# STM32F407ZGT6Floor.net
KiCad netlist of a schematic drawn in Altium Designer
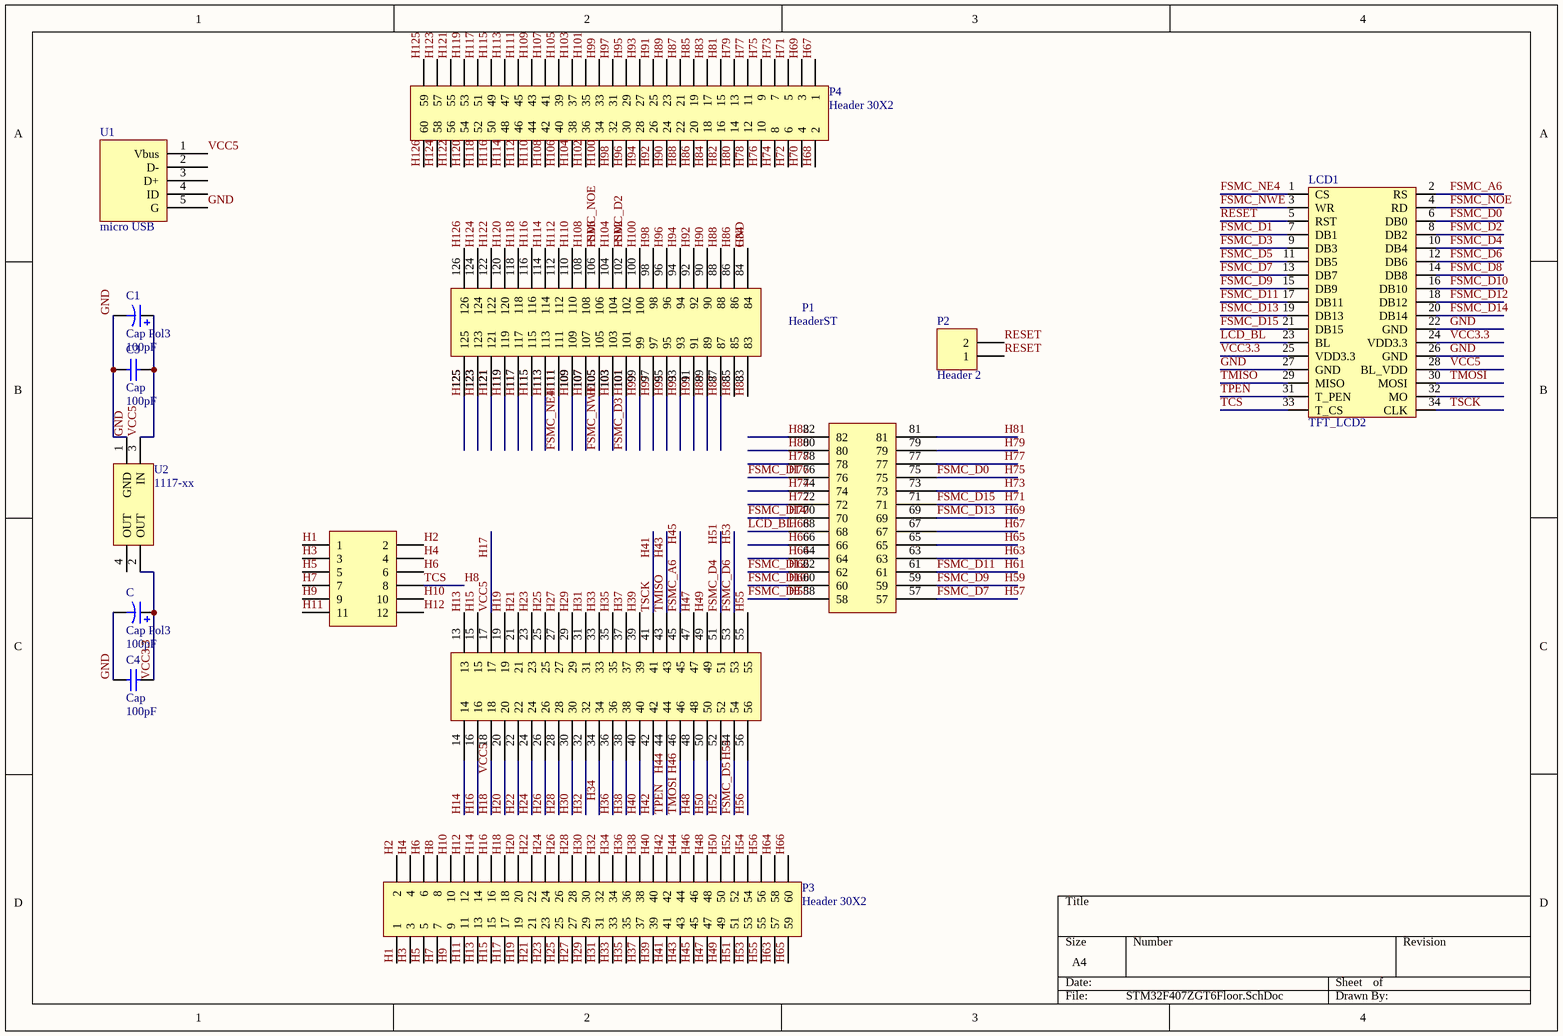
[diagram p0: STM32F407ZGT6Floor.SchDoc]

(export (version "E")
  (design (tool "Eeschema 10.0.6"))
  (components
    (comp (ref "C")
      (value "Cap Pol3")
      (footprint "CAP_SMD_3216")
      (description "Polarized Capacitor (Surface Mount)")
      (fields (field (name "ALTIUM_VALUE") "100pF") (field (name "PUBLISHER") "Altium Limited"))
      (libsource (lib "Miscellaneous Devices") (part "Cap Pol3"))
    )
    (comp (ref "C1")
      (value "Cap Pol3")
      (footprint "CAP_SMD_3216")
      (description "Polarized Capacitor (Surface Mount)")
      (fields (field (name "ALTIUM_VALUE") "100pF") (field (name "PUBLISHER") "Altium Limited"))
      (libsource (lib "Miscellaneous Devices") (part "Cap Pol3"))
    )
    (comp (ref "C3")
      (value "Cap")
      (footprint "0805C")
      (description "Capacitor")
      (fields (field (name "ALTIUM_VALUE") "100pF") (field (name "PUBLISHER") "Altium Limited"))
      (libsource (lib "Miscellaneous Devices") (part "Cap"))
    )
    (comp (ref "C4")
      (value "Cap")
      (footprint "0805C")
      (description "Capacitor")
      (fields (field (name "ALTIUM_VALUE") "100pF") (field (name "PUBLISHER") "Altium Limited"))
      (libsource (lib "Miscellaneous Devices") (part "Cap"))
    )
    (comp (ref "LCD1")
      (value "TFT_LCD2")
      (footprint "DB2*17-3.5")
      (libsource (lib "4.3TFTLCD") (part "TFT_LCD2"))
    )
    (comp (ref "P1")
      (value "HeaderST")
      (footprint "PCBComponent_1-1")
      (description "Header, 30-Pin, Dual row")
      (fields (field (name "PUBLISHER") "Altium Limited"))
      (libsource (lib "2-STM32F407ZGT6MINI原理图") (part "HeaderST"))
    )
    (comp (ref "P2")
      (value "Header 2")
      (footprint "HDR1X2")
      (description "Header, 2-Pin")
      (fields (field (name "PUBLISHER") "Altium Limited"))
      (libsource (lib "Miscellaneous Connectors") (part "Header 2"))
    )
    (comp (ref "P3")
      (value "Header 30X2")
      (footprint "HDR2X30")
      (description "Header, 30-Pin, Dual row")
      (fields (field (name "PUBLISHER") "Altium Limited"))
      (libsource (lib "") (part "Header 30X2_1"))
    )
    (comp (ref "P4")
      (value "Header 30X2")
      (footprint "HDR2X30")
      (description "Header, 30-Pin, Dual row")
      (fields (field (name "PUBLISHER") "Altium Limited"))
      (libsource (lib "Miscellaneous Connectors") (part "Header 30X2"))
    )
    (comp (ref "U1")
      (value "micro USB")
      (footprint "Micro_USB_v2 - duplicate")
      (libsource (lib "2-STM32F407ZGT6MINI原理图") (part "usb-STM"))
    )
    (comp (ref "U2")
      (value "1117-xx")
      (footprint "SOT-223_")
      (description "稳压芯片")
      (libsource (lib "unsal_Devices") (part "1117-xx"))
    )
  )
  (nets
    (net (code "1") (name "/FSMC_A6") (class "Default")
      (node (ref "LCD1") (pin "2") (pinfunction "RS_2") (pintype "passive"))
      (node (ref "P1") (pin "45") (pinfunction "45_45") (pintype "passive"))
      (node (ref "P3") (pin "45") (pinfunction "45_45") (pintype "passive"))
    )
    (net (code "2") (name "/FSMC_D0") (class "Default")
      (node (ref "LCD1") (pin "6") (pinfunction "DB0_6") (pintype "passive"))
      (node (ref "P1") (pin "75") (pinfunction "75_75") (pintype "passive"))
      (node (ref "P4") (pin "9") (pinfunction "9_9") (pintype "passive"))
    )
    (net (code "3") (name "/FSMC_D1") (class "Default")
      (node (ref "LCD1") (pin "7") (pinfunction "DB1_7") (pintype "passive"))
      (node (ref "P1") (pin "76") (pinfunction "76_76") (pintype "passive"))
      (node (ref "P4") (pin "10") (pinfunction "10_10") (pintype "passive"))
    )
    (net (code "4") (name "/FSMC_D2") (class "Default")
      (node (ref "LCD1") (pin "8") (pinfunction "DB2_8") (pintype "passive"))
      (node (ref "P1") (pin "102") (pinfunction "102_102") (pintype "passive"))
      (node (ref "P4") (pin "36") (pinfunction "36_36") (pintype "passive"))
    )
    (net (code "5") (name "/FSMC_D3") (class "Default")
      (node (ref "LCD1") (pin "9") (pinfunction "DB3_9") (pintype "passive"))
      (node (ref "P1") (pin "101") (pinfunction "101_101") (pintype "passive"))
      (node (ref "P4") (pin "35") (pinfunction "35_35") (pintype "passive"))
    )
    (net (code "6") (name "/FSMC_D4") (class "Default")
      (node (ref "LCD1") (pin "10") (pinfunction "DB4_10") (pintype "passive"))
      (node (ref "P1") (pin "51") (pinfunction "51_51") (pintype "passive"))
      (node (ref "P3") (pin "51") (pinfunction "51_51") (pintype "passive"))
    )
    (net (code "7") (name "/FSMC_D5") (class "Default")
      (node (ref "LCD1") (pin "11") (pinfunction "DB5_11") (pintype "passive"))
      (node (ref "P1") (pin "54") (pinfunction "54_54") (pintype "passive"))
      (node (ref "P3") (pin "54") (pinfunction "54_54") (pintype "passive"))
    )
    (net (code "8") (name "/FSMC_D6") (class "Default")
      (node (ref "LCD1") (pin "12") (pinfunction "DB6_12") (pintype "passive"))
      (node (ref "P1") (pin "53") (pinfunction "53_53") (pintype "passive"))
      (node (ref "P3") (pin "53") (pinfunction "53_53") (pintype "passive"))
    )
    (net (code "9") (name "/FSMC_D7") (class "Default")
      (node (ref "LCD1") (pin "13") (pinfunction "DB7_13") (pintype "passive"))
      (node (ref "P1") (pin "57") (pinfunction "57_57") (pintype "passive"))
    )
    (net (code "10") (name "/FSMC_D8") (class "Default")
      (node (ref "LCD1") (pin "14") (pinfunction "DB8_14") (pintype "passive"))
      (node (ref "P1") (pin "58") (pinfunction "58_58") (pintype "passive"))
    )
    (net (code "11") (name "/FSMC_D9") (class "Default")
      (node (ref "LCD1") (pin "15") (pinfunction "DB9_15") (pintype "passive"))
      (node (ref "P1") (pin "59") (pinfunction "59_59") (pintype "passive"))
    )
    (net (code "12") (name "/FSMC_D10") (class "Default")
      (node (ref "LCD1") (pin "16") (pinfunction "DB10_16") (pintype "passive"))
      (node (ref "P1") (pin "60") (pinfunction "60_60") (pintype "passive"))
    )
    (net (code "13") (name "/FSMC_D11") (class "Default")
      (node (ref "LCD1") (pin "17") (pinfunction "DB11_17") (pintype "passive"))
      (node (ref "P1") (pin "61") (pinfunction "61_61") (pintype "passive"))
    )
    (net (code "14") (name "/FSMC_D12") (class "Default")
      (node (ref "LCD1") (pin "18") (pinfunction "DB12_18") (pintype "passive"))
      (node (ref "P1") (pin "62") (pinfunction "62_62") (pintype "passive"))
    )
    (net (code "15") (name "/FSMC_D13") (class "Default")
      (node (ref "LCD1") (pin "19") (pinfunction "DB13_19") (pintype "passive"))
      (node (ref "P1") (pin "69") (pinfunction "69_69") (pintype "passive"))
      (node (ref "P4") (pin "3") (pinfunction "3_3") (pintype "passive"))
    )
    (net (code "16") (name "/FSMC_D14") (class "Default")
      (node (ref "LCD1") (pin "20") (pinfunction "DB14_20") (pintype "passive"))
      (node (ref "P1") (pin "70") (pinfunction "70_70") (pintype "passive"))
      (node (ref "P4") (pin "4") (pinfunction "4_4") (pintype "passive"))
    )
    (net (code "17") (name "/FSMC_D15") (class "Default")
      (node (ref "LCD1") (pin "21") (pinfunction "DB15_21") (pintype "passive"))
      (node (ref "P1") (pin "71") (pinfunction "71_71") (pintype "passive"))
      (node (ref "P4") (pin "5") (pinfunction "5_5") (pintype "passive"))
    )
    (net (code "18") (name "/FSMC_NE4") (class "Default")
      (node (ref "LCD1") (pin "1") (pinfunction "CS_1") (pintype "passive"))
      (node (ref "P1") (pin "111") (pinfunction "111_111") (pintype "passive"))
      (node (ref "P4") (pin "45") (pinfunction "45_45") (pintype "passive"))
    )
    (net (code "19") (name "/FSMC_NOE") (class "Default")
      (node (ref "LCD1") (pin "4") (pinfunction "RD_4") (pintype "passive"))
      (node (ref "P1") (pin "106") (pinfunction "106_106") (pintype "passive"))
      (node (ref "P4") (pin "40") (pinfunction "40_40") (pintype "passive"))
    )
    (net (code "20") (name "/FSMC_NWE") (class "Default")
      (node (ref "LCD1") (pin "3") (pinfunction "WR_3") (pintype "passive"))
      (node (ref "P1") (pin "105") (pinfunction "105_105") (pintype "passive"))
      (node (ref "P4") (pin "39") (pinfunction "39_39") (pintype "passive"))
    )
    (net (code "21") (name "/GND") (class "Default")
      (node (ref "C") (pin "2") (pinfunction "2_2") (pintype "passive"))
      (node (ref "C1") (pin "2") (pinfunction "2_2") (pintype "passive"))
      (node (ref "C3") (pin "1") (pinfunction "1_1") (pintype "passive"))
      (node (ref "C4") (pin "1") (pinfunction "1_1") (pintype "passive"))
      (node (ref "LCD1") (pin "22") (pinfunction "GND_22") (pintype "passive"))
      (node (ref "LCD1") (pin "26") (pinfunction "GND_26") (pintype "passive"))
      (node (ref "LCD1") (pin "27") (pinfunction "GND_27") (pintype "passive"))
      (node (ref "P1") (pin "84") (pinfunction "84_84") (pintype "passive"))
      (node (ref "P4") (pin "18") (pinfunction "18_18") (pintype "passive"))
      (node (ref "U1") (pin "5") (pinfunction "G_5") (pintype "passive"))
      (node (ref "U2") (pin "1") (pinfunction "GND_1") (pintype "passive"))
    )
    (net (code "22") (name "/H1") (class "Default")
      (node (ref "P1") (pin "1") (pinfunction "1_1") (pintype "passive"))
      (node (ref "P3") (pin "1") (pinfunction "1_1") (pintype "passive"))
    )
    (net (code "23") (name "/H2") (class "Default")
      (node (ref "P1") (pin "2") (pinfunction "2_2") (pintype "passive"))
      (node (ref "P3") (pin "2") (pinfunction "2_2") (pintype "passive"))
    )
    (net (code "24") (name "/H3") (class "Default")
      (node (ref "P1") (pin "3") (pinfunction "3_3") (pintype "passive"))
      (node (ref "P3") (pin "3") (pinfunction "3_3") (pintype "passive"))
    )
    (net (code "25") (name "/H4") (class "Default")
      (node (ref "P1") (pin "4") (pinfunction "4_4") (pintype "passive"))
      (node (ref "P3") (pin "4") (pinfunction "4_4") (pintype "passive"))
    )
    (net (code "26") (name "/H5") (class "Default")
      (node (ref "P1") (pin "5") (pinfunction "5_5") (pintype "passive"))
      (node (ref "P3") (pin "5") (pinfunction "5_5") (pintype "passive"))
    )
    (net (code "27") (name "/H6") (class "Default")
      (node (ref "P1") (pin "6") (pinfunction "6_6") (pintype "passive"))
      (node (ref "P3") (pin "6") (pinfunction "6_6") (pintype "passive"))
    )
    (net (code "28") (name "/H7") (class "Default")
      (node (ref "P1") (pin "7") (pinfunction "7_7") (pintype "passive"))
      (node (ref "P3") (pin "7") (pinfunction "7_7") (pintype "passive"))
    )
    (net (code "29") (name "/H8") (class "Default")
      (node (ref "LCD1") (pin "33") (pinfunction "T_CS_33") (pintype "passive"))
      (node (ref "P1") (pin "8") (pinfunction "8_8") (pintype "passive"))
      (node (ref "P3") (pin "8") (pinfunction "8_8") (pintype "passive"))
    )
    (net (code "30") (name "/H9") (class "Default")
      (node (ref "P1") (pin "9") (pinfunction "9_9") (pintype "passive"))
      (node (ref "P3") (pin "9") (pinfunction "9_9") (pintype "passive"))
    )
    (net (code "31") (name "/H10") (class "Default")
      (node (ref "P1") (pin "10") (pinfunction "10_10") (pintype "passive"))
      (node (ref "P3") (pin "10") (pinfunction "10_10") (pintype "passive"))
    )
    (net (code "32") (name "/H11") (class "Default")
      (node (ref "P1") (pin "11") (pinfunction "11_11") (pintype "passive"))
      (node (ref "P3") (pin "11") (pinfunction "11_11") (pintype "passive"))
    )
    (net (code "33") (name "/H12") (class "Default")
      (node (ref "P1") (pin "12") (pinfunction "12_12") (pintype "passive"))
      (node (ref "P3") (pin "12") (pinfunction "12_12") (pintype "passive"))
    )
    (net (code "34") (name "/H13") (class "Default")
      (node (ref "P1") (pin "13") (pinfunction "13_13") (pintype "passive"))
      (node (ref "P3") (pin "13") (pinfunction "13_13") (pintype "passive"))
    )
    (net (code "35") (name "/H14") (class "Default")
      (node (ref "P1") (pin "14") (pinfunction "14_14") (pintype "passive"))
      (node (ref "P3") (pin "14") (pinfunction "14_14") (pintype "passive"))
    )
    (net (code "36") (name "/H15") (class "Default")
      (node (ref "P1") (pin "15") (pinfunction "15_15") (pintype "passive"))
      (node (ref "P3") (pin "15") (pinfunction "15_15") (pintype "passive"))
    )
    (net (code "37") (name "/H16") (class "Default")
      (node (ref "P1") (pin "16") (pinfunction "16_16") (pintype "passive"))
      (node (ref "P3") (pin "16") (pinfunction "16_16") (pintype "passive"))
    )
    (net (code "38") (name "/H17") (class "Default")
      (node (ref "C1") (pin "1") (pinfunction "1_1") (pintype "passive"))
      (node (ref "C3") (pin "2") (pinfunction "2_2") (pintype "passive"))
      (node (ref "LCD1") (pin "28") (pinfunction "BL_VDD_28") (pintype "passive"))
      (node (ref "P1") (pin "17") (pinfunction "17_17") (pintype "passive"))
      (node (ref "P1") (pin "18") (pinfunction "18_18") (pintype "passive"))
      (node (ref "P3") (pin "17") (pinfunction "17_17") (pintype "passive"))
      (node (ref "P3") (pin "18") (pinfunction "18_18") (pintype "passive"))
      (node (ref "U1") (pin "1") (pinfunction "Vbus_1") (pintype "passive"))
      (node (ref "U2") (pin "3") (pinfunction "IN_3") (pintype "passive"))
    )
    (net (code "39") (name "/H19") (class "Default")
      (node (ref "P1") (pin "19") (pinfunction "19_19") (pintype "passive"))
      (node (ref "P3") (pin "19") (pinfunction "19_19") (pintype "passive"))
    )
    (net (code "40") (name "/H20") (class "Default")
      (node (ref "P1") (pin "20") (pinfunction "20_20") (pintype "passive"))
      (node (ref "P3") (pin "20") (pinfunction "20_20") (pintype "passive"))
    )
    (net (code "41") (name "/H21") (class "Default")
      (node (ref "P1") (pin "21") (pinfunction "21_21") (pintype "passive"))
      (node (ref "P3") (pin "21") (pinfunction "21_21") (pintype "passive"))
    )
    (net (code "42") (name "/H22") (class "Default")
      (node (ref "P1") (pin "22") (pinfunction "22_22") (pintype "passive"))
      (node (ref "P3") (pin "22") (pinfunction "22_22") (pintype "passive"))
    )
    (net (code "43") (name "/H23") (class "Default")
      (node (ref "P1") (pin "23") (pinfunction "23_23") (pintype "passive"))
      (node (ref "P3") (pin "23") (pinfunction "23_23") (pintype "passive"))
    )
    (net (code "44") (name "/H24") (class "Default")
      (node (ref "P1") (pin "24") (pinfunction "24_24") (pintype "passive"))
      (node (ref "P3") (pin "24") (pinfunction "24_24") (pintype "passive"))
    )
    (net (code "45") (name "/H25") (class "Default")
      (node (ref "P1") (pin "25") (pinfunction "25_25") (pintype "passive"))
      (node (ref "P3") (pin "25") (pinfunction "25_25") (pintype "passive"))
    )
    (net (code "46") (name "/H26") (class "Default")
      (node (ref "P1") (pin "26") (pinfunction "26_26") (pintype "passive"))
      (node (ref "P3") (pin "26") (pinfunction "26_26") (pintype "passive"))
    )
    (net (code "47") (name "/H27") (class "Default")
      (node (ref "P1") (pin "27") (pinfunction "27_27") (pintype "passive"))
      (node (ref "P3") (pin "27") (pinfunction "27_27") (pintype "passive"))
    )
    (net (code "48") (name "/H28") (class "Default")
      (node (ref "P1") (pin "28") (pinfunction "28_28") (pintype "passive"))
      (node (ref "P3") (pin "28") (pinfunction "28_28") (pintype "passive"))
    )
    (net (code "49") (name "/H29") (class "Default")
      (node (ref "P1") (pin "29") (pinfunction "29_29") (pintype "passive"))
      (node (ref "P3") (pin "29") (pinfunction "29_29") (pintype "passive"))
    )
    (net (code "50") (name "/H30") (class "Default")
      (node (ref "P1") (pin "30") (pinfunction "30_30") (pintype "passive"))
      (node (ref "P3") (pin "30") (pinfunction "30_30") (pintype "passive"))
    )
    (net (code "51") (name "/H31") (class "Default")
      (node (ref "P1") (pin "31") (pinfunction "31_31") (pintype "passive"))
      (node (ref "P3") (pin "31") (pinfunction "31_31") (pintype "passive"))
    )
    (net (code "52") (name "/H32") (class "Default")
      (node (ref "P1") (pin "32") (pinfunction "32_32") (pintype "passive"))
      (node (ref "P3") (pin "32") (pinfunction "32_32") (pintype "passive"))
    )
    (net (code "53") (name "/H33") (class "Default")
      (node (ref "P1") (pin "33") (pinfunction "33_33") (pintype "passive"))
      (node (ref "P3") (pin "33") (pinfunction "33_33") (pintype "passive"))
    )
    (net (code "54") (name "/H34") (class "Default")
      (node (ref "P1") (pin "34") (pinfunction "34_34") (pintype "passive"))
      (node (ref "P3") (pin "34") (pinfunction "34_34") (pintype "passive"))
    )
    (net (code "55") (name "/H35") (class "Default")
      (node (ref "P1") (pin "35") (pinfunction "35_35") (pintype "passive"))
      (node (ref "P3") (pin "35") (pinfunction "35_35") (pintype "passive"))
    )
    (net (code "56") (name "/H36") (class "Default")
      (node (ref "P1") (pin "36") (pinfunction "36_36") (pintype "passive"))
      (node (ref "P3") (pin "36") (pinfunction "36_36") (pintype "passive"))
    )
    (net (code "57") (name "/H37") (class "Default")
      (node (ref "P1") (pin "37") (pinfunction "37_37") (pintype "passive"))
      (node (ref "P3") (pin "37") (pinfunction "37_37") (pintype "passive"))
    )
    (net (code "58") (name "/H38") (class "Default")
      (node (ref "P1") (pin "38") (pinfunction "38_38") (pintype "passive"))
      (node (ref "P3") (pin "38") (pinfunction "38_38") (pintype "passive"))
    )
    (net (code "59") (name "/H39") (class "Default")
      (node (ref "P1") (pin "39") (pinfunction "39_39") (pintype "passive"))
      (node (ref "P3") (pin "39") (pinfunction "39_39") (pintype "passive"))
    )
    (net (code "60") (name "/H40") (class "Default")
      (node (ref "P1") (pin "40") (pinfunction "40_40") (pintype "passive"))
      (node (ref "P3") (pin "40") (pinfunction "40_40") (pintype "passive"))
    )
    (net (code "61") (name "/H41") (class "Default")
      (node (ref "LCD1") (pin "34") (pinfunction "CLK_34") (pintype "passive"))
      (node (ref "P1") (pin "41") (pinfunction "41_41") (pintype "passive"))
      (node (ref "P3") (pin "41") (pinfunction "41_41") (pintype "passive"))
    )
    (net (code "62") (name "/H42") (class "Default")
      (node (ref "P1") (pin "42") (pinfunction "42_42") (pintype "passive"))
      (node (ref "P3") (pin "42") (pinfunction "42_42") (pintype "passive"))
    )
    (net (code "63") (name "/H43") (class "Default")
      (node (ref "LCD1") (pin "29") (pinfunction "MISO_29") (pintype "passive"))
      (node (ref "P1") (pin "43") (pinfunction "43_43") (pintype "passive"))
      (node (ref "P3") (pin "43") (pinfunction "43_43") (pintype "passive"))
    )
    (net (code "64") (name "/H44") (class "Default")
      (node (ref "LCD1") (pin "31") (pinfunction "T_PEN_31") (pintype "passive"))
      (node (ref "P1") (pin "44") (pinfunction "44_44") (pintype "passive"))
      (node (ref "P3") (pin "44") (pinfunction "44_44") (pintype "passive"))
    )
    (net (code "65") (name "/H46") (class "Default")
      (node (ref "LCD1") (pin "30") (pinfunction "MOSI_30") (pintype "passive"))
      (node (ref "P1") (pin "46") (pinfunction "46_46") (pintype "passive"))
      (node (ref "P3") (pin "46") (pinfunction "46_46") (pintype "passive"))
    )
    (net (code "66") (name "/H47") (class "Default")
      (node (ref "P1") (pin "47") (pinfunction "47_47") (pintype "passive"))
      (node (ref "P3") (pin "47") (pinfunction "47_47") (pintype "passive"))
    )
    (net (code "67") (name "/H48") (class "Default")
      (node (ref "P1") (pin "48") (pinfunction "48_48") (pintype "passive"))
      (node (ref "P3") (pin "48") (pinfunction "48_48") (pintype "passive"))
    )
    (net (code "68") (name "/H49") (class "Default")
      (node (ref "P1") (pin "49") (pinfunction "49_49") (pintype "passive"))
      (node (ref "P3") (pin "49") (pinfunction "49_49") (pintype "passive"))
    )
    (net (code "69") (name "/H50") (class "Default")
      (node (ref "P1") (pin "50") (pinfunction "50_50") (pintype "passive"))
      (node (ref "P3") (pin "50") (pinfunction "50_50") (pintype "passive"))
    )
    (net (code "70") (name "/H52") (class "Default")
      (node (ref "P1") (pin "52") (pinfunction "52_52") (pintype "passive"))
      (node (ref "P3") (pin "52") (pinfunction "52_52") (pintype "passive"))
    )
    (net (code "71") (name "/H55") (class "Default")
      (node (ref "P1") (pin "55") (pinfunction "55_55") (pintype "passive"))
      (node (ref "P3") (pin "55") (pinfunction "55_55") (pintype "passive"))
    )
    (net (code "72") (name "/H56") (class "Default")
      (node (ref "P1") (pin "56") (pinfunction "56_56") (pintype "passive"))
      (node (ref "P3") (pin "56") (pinfunction "56_56") (pintype "passive"))
    )
    (net (code "73") (name "/H63") (class "Default")
      (node (ref "P1") (pin "63") (pinfunction "63_63") (pintype "passive"))
      (node (ref "P3") (pin "57") (pinfunction "57_57") (pintype "passive"))
    )
    (net (code "74") (name "/H64") (class "Default")
      (node (ref "P1") (pin "64") (pinfunction "64_64") (pintype "passive"))
      (node (ref "P3") (pin "58") (pinfunction "58_58") (pintype "passive"))
    )
    (net (code "75") (name "/H65") (class "Default")
      (node (ref "P1") (pin "65") (pinfunction "65_65") (pintype "passive"))
      (node (ref "P3") (pin "59") (pinfunction "59_59") (pintype "passive"))
    )
    (net (code "76") (name "/H66") (class "Default")
      (node (ref "P1") (pin "66") (pinfunction "66_66") (pintype "passive"))
      (node (ref "P3") (pin "60") (pinfunction "60_60") (pintype "passive"))
    )
    (net (code "77") (name "/H67") (class "Default")
      (node (ref "P1") (pin "67") (pinfunction "67_67") (pintype "passive"))
      (node (ref "P4") (pin "1") (pinfunction "1_1") (pintype "passive"))
    )
    (net (code "78") (name "/H68") (class "Default")
      (node (ref "LCD1") (pin "23") (pinfunction "BL_23") (pintype "passive"))
      (node (ref "P1") (pin "68") (pinfunction "68_68") (pintype "passive"))
      (node (ref "P4") (pin "2") (pinfunction "2_2") (pintype "passive"))
    )
    (net (code "79") (name "/H72") (class "Default")
      (node (ref "P1") (pin "72") (pinfunction "72_72") (pintype "passive"))
      (node (ref "P4") (pin "6") (pinfunction "6_6") (pintype "passive"))
    )
    (net (code "80") (name "/H73") (class "Default")
      (node (ref "P1") (pin "73") (pinfunction "73_73") (pintype "passive"))
      (node (ref "P4") (pin "7") (pinfunction "7_7") (pintype "passive"))
    )
    (net (code "81") (name "/H74") (class "Default")
      (node (ref "P1") (pin "74") (pinfunction "74_74") (pintype "passive"))
      (node (ref "P4") (pin "8") (pinfunction "8_8") (pintype "passive"))
    )
    (net (code "82") (name "/H77") (class "Default")
      (node (ref "P1") (pin "77") (pinfunction "77_77") (pintype "passive"))
      (node (ref "P4") (pin "11") (pinfunction "11_11") (pintype "passive"))
    )
    (net (code "83") (name "/H78") (class "Default")
      (node (ref "P1") (pin "78") (pinfunction "78_78") (pintype "passive"))
      (node (ref "P4") (pin "12") (pinfunction "12_12") (pintype "passive"))
    )
    (net (code "84") (name "/H79") (class "Default")
      (node (ref "P1") (pin "79") (pinfunction "79_79") (pintype "passive"))
      (node (ref "P4") (pin "13") (pinfunction "13_13") (pintype "passive"))
    )
    (net (code "85") (name "/H80") (class "Default")
      (node (ref "P1") (pin "80") (pinfunction "80_80") (pintype "passive"))
      (node (ref "P4") (pin "14") (pinfunction "14_14") (pintype "passive"))
    )
    (net (code "86") (name "/H81") (class "Default")
      (node (ref "P1") (pin "81") (pinfunction "81_81") (pintype "passive"))
      (node (ref "P4") (pin "15") (pinfunction "15_15") (pintype "passive"))
    )
    (net (code "87") (name "/H82") (class "Default")
      (node (ref "P1") (pin "82") (pinfunction "82_82") (pintype "passive"))
      (node (ref "P4") (pin "16") (pinfunction "16_16") (pintype "passive"))
    )
    (net (code "88") (name "/H83") (class "Default")
      (node (ref "P1") (pin "83") (pinfunction "83_83") (pintype "passive"))
      (node (ref "P4") (pin "17") (pinfunction "17_17") (pintype "passive"))
    )
    (net (code "89") (name "/H85") (class "Default")
      (node (ref "P1") (pin "85") (pinfunction "85_85") (pintype "passive"))
      (node (ref "P4") (pin "19") (pinfunction "19_19") (pintype "passive"))
    )
    (net (code "90") (name "/H86") (class "Default")
      (node (ref "P1") (pin "86") (pinfunction "86_86") (pintype "passive"))
      (node (ref "P4") (pin "20") (pinfunction "20_20") (pintype "passive"))
    )
    (net (code "91") (name "/H87") (class "Default")
      (node (ref "P1") (pin "87") (pinfunction "87_87") (pintype "passive"))
      (node (ref "P4") (pin "21") (pinfunction "21_21") (pintype "passive"))
    )
    (net (code "92") (name "/H88") (class "Default")
      (node (ref "P1") (pin "88") (pinfunction "88_88") (pintype "passive"))
      (node (ref "P4") (pin "22") (pinfunction "22_22") (pintype "passive"))
    )
    (net (code "93") (name "/H89") (class "Default")
      (node (ref "P1") (pin "89") (pinfunction "89_89") (pintype "passive"))
      (node (ref "P4") (pin "23") (pinfunction "23_23") (pintype "passive"))
    )
    (net (code "94") (name "/H90") (class "Default")
      (node (ref "P1") (pin "90") (pinfunction "90_90") (pintype "passive"))
      (node (ref "P4") (pin "24") (pinfunction "24_24") (pintype "passive"))
    )
    (net (code "95") (name "/H91") (class "Default")
      (node (ref "P1") (pin "91") (pinfunction "91_91") (pintype "passive"))
      (node (ref "P4") (pin "25") (pinfunction "25_25") (pintype "passive"))
    )
    (net (code "96") (name "/H92") (class "Default")
      (node (ref "P1") (pin "92") (pinfunction "92_92") (pintype "passive"))
      (node (ref "P4") (pin "26") (pinfunction "26_26") (pintype "passive"))
    )
    (net (code "97") (name "/H93") (class "Default")
      (node (ref "P1") (pin "93") (pinfunction "93_93") (pintype "passive"))
      (node (ref "P4") (pin "27") (pinfunction "27_27") (pintype "passive"))
    )
    (net (code "98") (name "/H94") (class "Default")
      (node (ref "P1") (pin "94") (pinfunction "94_94") (pintype "passive"))
      (node (ref "P4") (pin "28") (pinfunction "28_28") (pintype "passive"))
    )
    (net (code "99") (name "/H95") (class "Default")
      (node (ref "P1") (pin "95") (pinfunction "95_95") (pintype "passive"))
      (node (ref "P4") (pin "29") (pinfunction "29_29") (pintype "passive"))
    )
    (net (code "100") (name "/H96") (class "Default")
      (node (ref "P1") (pin "96") (pinfunction "96_96") (pintype "passive"))
      (node (ref "P4") (pin "30") (pinfunction "30_30") (pintype "passive"))
    )
    (net (code "101") (name "/H97") (class "Default")
      (node (ref "P1") (pin "97") (pinfunction "97_97") (pintype "passive"))
      (node (ref "P4") (pin "31") (pinfunction "31_31") (pintype "passive"))
    )
    (net (code "102") (name "/H98") (class "Default")
      (node (ref "P1") (pin "98") (pinfunction "98_98") (pintype "passive"))
      (node (ref "P4") (pin "32") (pinfunction "32_32") (pintype "passive"))
    )
    (net (code "103") (name "/H99") (class "Default")
      (node (ref "P1") (pin "99") (pinfunction "99_99") (pintype "passive"))
      (node (ref "P4") (pin "33") (pinfunction "33_33") (pintype "passive"))
    )
    (net (code "104") (name "/H100") (class "Default")
      (node (ref "P1") (pin "100") (pinfunction "100_100") (pintype "passive"))
      (node (ref "P4") (pin "34") (pinfunction "34_34") (pintype "passive"))
    )
    (net (code "105") (name "/H103") (class "Default")
      (node (ref "P1") (pin "103") (pinfunction "103_103") (pintype "passive"))
      (node (ref "P4") (pin "37") (pinfunction "37_37") (pintype "passive"))
    )
    (net (code "106") (name "/H104") (class "Default")
      (node (ref "P1") (pin "104") (pinfunction "104_104") (pintype "passive"))
      (node (ref "P4") (pin "38") (pinfunction "38_38") (pintype "passive"))
    )
    (net (code "107") (name "/H107") (class "Default")
      (node (ref "P1") (pin "107") (pinfunction "107_107") (pintype "passive"))
      (node (ref "P4") (pin "41") (pinfunction "41_41") (pintype "passive"))
    )
    (net (code "108") (name "/H108") (class "Default")
      (node (ref "P1") (pin "108") (pinfunction "108_108") (pintype "passive"))
      (node (ref "P4") (pin "42") (pinfunction "42_42") (pintype "passive"))
    )
    (net (code "109") (name "/H109") (class "Default")
      (node (ref "P1") (pin "109") (pinfunction "109_109") (pintype "passive"))
      (node (ref "P4") (pin "43") (pinfunction "43_43") (pintype "passive"))
    )
    (net (code "110") (name "/H110") (class "Default")
      (node (ref "P1") (pin "110") (pinfunction "110_110") (pintype "passive"))
      (node (ref "P4") (pin "44") (pinfunction "44_44") (pintype "passive"))
    )
    (net (code "111") (name "/H112") (class "Default")
      (node (ref "P1") (pin "112") (pinfunction "112_112") (pintype "passive"))
      (node (ref "P4") (pin "46") (pinfunction "46_46") (pintype "passive"))
    )
    (net (code "112") (name "/H113") (class "Default")
      (node (ref "P1") (pin "113") (pinfunction "113_113") (pintype "passive"))
      (node (ref "P4") (pin "47") (pinfunction "47_47") (pintype "passive"))
    )
    (net (code "113") (name "/H114") (class "Default")
      (node (ref "P1") (pin "114") (pinfunction "114_114") (pintype "passive"))
      (node (ref "P4") (pin "48") (pinfunction "48_48") (pintype "passive"))
    )
    (net (code "114") (name "/H115") (class "Default")
      (node (ref "P1") (pin "115") (pinfunction "115_115") (pintype "passive"))
      (node (ref "P4") (pin "49") (pinfunction "49_49") (pintype "passive"))
    )
    (net (code "115") (name "/H116") (class "Default")
      (node (ref "P1") (pin "116") (pinfunction "116_116") (pintype "passive"))
      (node (ref "P4") (pin "50") (pinfunction "50_50") (pintype "passive"))
    )
    (net (code "116") (name "/H117") (class "Default")
      (node (ref "P1") (pin "117") (pinfunction "117_117") (pintype "passive"))
      (node (ref "P4") (pin "51") (pinfunction "51_51") (pintype "passive"))
    )
    (net (code "117") (name "/H118") (class "Default")
      (node (ref "P1") (pin "118") (pinfunction "118_118") (pintype "passive"))
      (node (ref "P4") (pin "52") (pinfunction "52_52") (pintype "passive"))
    )
    (net (code "118") (name "/H119") (class "Default")
      (node (ref "P1") (pin "119") (pinfunction "119_119") (pintype "passive"))
      (node (ref "P4") (pin "53") (pinfunction "53_53") (pintype "passive"))
    )
    (net (code "119") (name "/H120") (class "Default")
      (node (ref "P1") (pin "120") (pinfunction "120_120") (pintype "passive"))
      (node (ref "P4") (pin "54") (pinfunction "54_54") (pintype "passive"))
    )
    (net (code "120") (name "/H121") (class "Default")
      (node (ref "P1") (pin "121") (pinfunction "121_121") (pintype "passive"))
      (node (ref "P4") (pin "55") (pinfunction "55_55") (pintype "passive"))
    )
    (net (code "121") (name "/H122") (class "Default")
      (node (ref "P1") (pin "122") (pinfunction "122_122") (pintype "passive"))
      (node (ref "P4") (pin "56") (pinfunction "56_56") (pintype "passive"))
    )
    (net (code "122") (name "/H123") (class "Default")
      (node (ref "P1") (pin "123") (pinfunction "123_123") (pintype "passive"))
      (node (ref "P4") (pin "57") (pinfunction "57_57") (pintype "passive"))
    )
    (net (code "123") (name "/H124") (class "Default")
      (node (ref "P1") (pin "124") (pinfunction "124_124") (pintype "passive"))
      (node (ref "P4") (pin "58") (pinfunction "58_58") (pintype "passive"))
    )
    (net (code "124") (name "/H125") (class "Default")
      (node (ref "P1") (pin "125") (pinfunction "125_125") (pintype "passive"))
      (node (ref "P4") (pin "59") (pinfunction "59_59") (pintype "passive"))
    )
    (net (code "125") (name "/H126") (class "Default")
      (node (ref "P1") (pin "126") (pinfunction "126_126") (pintype "passive"))
      (node (ref "P4") (pin "60") (pinfunction "60_60") (pintype "passive"))
    )
    (net (code "126") (name "/RESET") (class "Default")
      (node (ref "LCD1") (pin "5") (pinfunction "RST_5") (pintype "passive"))
      (node (ref "P2") (pin "1") (pinfunction "1_1") (pintype "passive"))
      (node (ref "P2") (pin "2") (pinfunction "2_2") (pintype "passive"))
    )
    (net (code "127") (name "/VCC3.3") (class "Default")
      (node (ref "C") (pin "1") (pinfunction "1_1") (pintype "passive"))
      (node (ref "C4") (pin "2") (pinfunction "2_2") (pintype "passive"))
      (node (ref "LCD1") (pin "24") (pinfunction "VDD3.3_24") (pintype "passive"))
      (node (ref "LCD1") (pin "25") (pinfunction "VDD3.3_25") (pintype "passive"))
      (node (ref "U2") (pin "2") (pinfunction "OUT_2") (pintype "passive"))
    )
    (net (code "128") (name "unconnected-(LCD1-MO-Pad32)") (class "Default")
      (node (ref "LCD1") (pin "32") (pinfunction "MO_32") (pintype "passive"))
    )
    (net (code "129") (name "unconnected-(U1-D+-Pad3)") (class "Default")
      (node (ref "U1") (pin "3") (pinfunction "D+_3") (pintype "passive"))
    )
    (net (code "130") (name "unconnected-(U1-D--Pad2)") (class "Default")
      (node (ref "U1") (pin "2") (pinfunction "D-_2") (pintype "passive"))
    )
    (net (code "131") (name "unconnected-(U1-ID-Pad4)") (class "Default")
      (node (ref "U1") (pin "4") (pinfunction "ID_4") (pintype "passive"))
    )
    (net (code "132") (name "unconnected-(U2-OUT-Pad4)") (class "Default")
      (node (ref "U2") (pin "4") (pinfunction "OUT_4") (pintype "passive"))
    )
  )
)
